# power_simp.net
KiCad netlist of a schematic drawn in Altium Designer
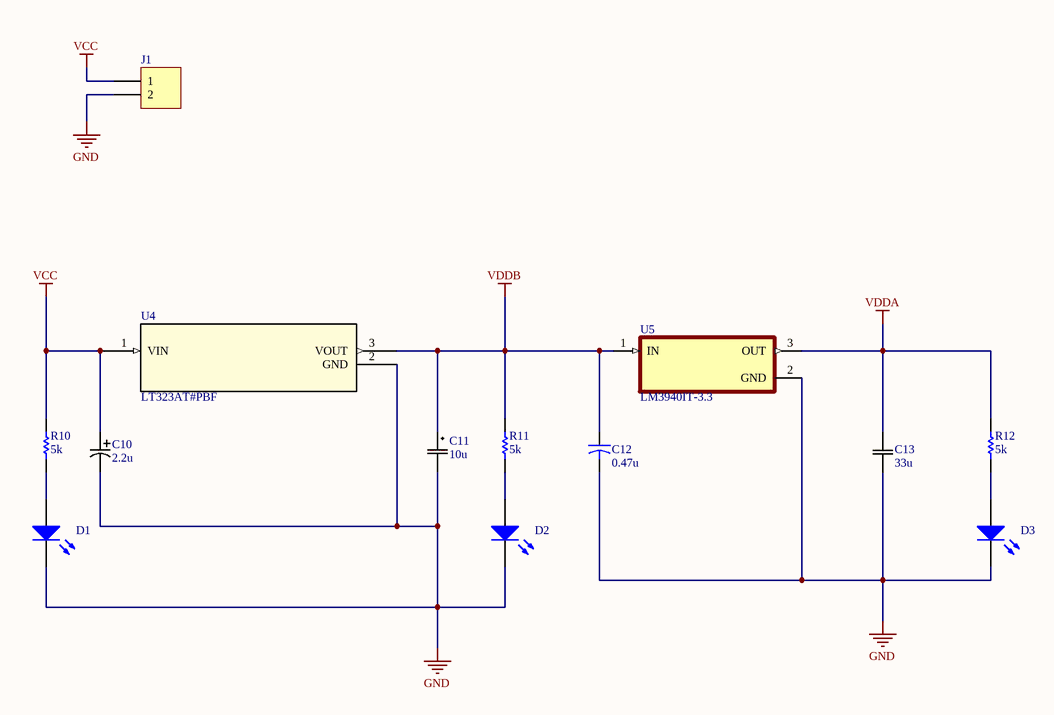
[diagram p0: power_simp.SchDoc]

(export (version "E")
  (design (tool "Eeschema 10.0.6"))
  (components
    (comp (ref "C10")
      (value "2.2u")
      (footprint "PCAP_3x5-THRU-ELECT_NCA")
      (description "No Description Available")
      (libsource (lib "UMA1V2R2MCD2") (part "UMA1V2R2MCD2"))
    )
    (comp (ref "C11")
      (value "10u")
      (footprint "CAP_UHC_4X7_NCH")
      (description "No Description Available")
      (libsource (lib "USR1E100MDD1TE") (part "USR1E100MDD1TE"))
    )
    (comp (ref "C12")
      (value "0.47u")
      (footprint "CAPR5-4X5")
      (description "Capacitor")
      (fields (field (name "Comment") "Cap2") (field (name "PUBLISHER") "Altium Limited"))
      (libsource (lib "Miscellaneous Devices") (part "Cap2"))
    )
    (comp (ref "C13")
      (value "33u")
      (footprint "CAP_FG16X5R1E336MRT06_TDK")
      (description "No Description Available")
      (libsource (lib "FG16X5R1E336MRT06") (part "FG16X5R1E336MRT06"))
    )
    (comp (ref "D1")
      (value "LED1")
      (footprint "LED-1")
      (description "Typical RED GaAs LED")
      (fields (field (name "PUBLISHER") "Altium Limited"))
      (libsource (lib "Miscellaneous Devices") (part "LED1"))
    )
    (comp (ref "D2")
      (value "LED1")
      (footprint "LED-1")
      (description "Typical RED GaAs LED")
      (fields (field (name "PUBLISHER") "Altium Limited"))
      (libsource (lib "Miscellaneous Devices") (part "LED1"))
    )
    (comp (ref "D3")
      (value "LED1")
      (footprint "LED-1")
      (description "Typical RED GaAs LED")
      (fields (field (name "PUBLISHER") "Altium Limited"))
      (libsource (lib "Miscellaneous Devices") (part "LED1"))
    )
    (comp (ref "J1")
      (value "Header 2")
      (footprint "HDR1X2")
      (description "Header, 2-Pin")
      (fields (field (name "PUBLISHER") "Altium Limited"))
      (libsource (lib "Miscellaneous Connectors") (part "Header 2"))
    )
    (comp (ref "R10")
      (value "5k")
      (footprint "AXIAL-0.3")
      (description "Resistor")
      (fields (field (name "Comment") "Res1") (field (name "PUBLISHER") "Altium Limited"))
      (libsource (lib "Miscellaneous Devices") (part "Res1"))
    )
    (comp (ref "R11")
      (value "5k")
      (footprint "AXIAL-0.3")
      (description "Resistor")
      (fields (field (name "Comment") "Res1") (field (name "PUBLISHER") "Altium Limited"))
      (libsource (lib "Miscellaneous Devices") (part "Res1"))
    )
    (comp (ref "R12")
      (value "5k")
      (footprint "AXIAL-0.3")
      (description "Resistor")
      (fields (field (name "Comment") "Res1") (field (name "PUBLISHER") "Altium Limited"))
      (libsource (lib "Miscellaneous Devices") (part "Res1"))
    )
    (comp (ref "U4")
      (value "LT323AT#PBF")
      (footprint "TO-220-AB")
      (description "No Description Available")
      (fields (field (name "COPYRIGHT") "Copyright (C) 2022 Ultra Librarian. All rights reserved."))
      (libsource (lib "LT323AT&hash_PBF") (part "LT323AT#PBF"))
    )
    (comp (ref "U5")
      (value "LM3940IT-3.3")
      (footprint "TO254P1054X470X1955-3:TO254P1054X470X1955-3")
      (description "1-A, low-dropout voltage regulator for 5-V to 3.3-V conversion 3-TO-220 -40 to 125")
      (fields (field (name "MF") "Texas Instruments"))
      (libsource (lib "LM3940IT-3.3") (part "LM3940IT-3.3"))
    )
  )
  (nets
    (net (code "1") (name "GND") (class "Default")
      (node (ref "C10") (pin "2") (pinfunction "2_2") (pintype "passive"))
      (node (ref "C11") (pin "2") (pinfunction "2_2") (pintype "passive"))
      (node (ref "C12") (pin "2") (pinfunction "2_2") (pintype "passive"))
      (node (ref "C13") (pin "1") (pinfunction "1_1") (pintype "passive"))
      (node (ref "D1") (pin "2") (pinfunction "K_2") (pintype "passive"))
      (node (ref "D2") (pin "2") (pinfunction "K_2") (pintype "passive"))
      (node (ref "D3") (pin "2") (pinfunction "K_2") (pintype "passive"))
      (node (ref "J1") (pin "2") (pinfunction "2_2") (pintype "passive"))
      (node (ref "U4") (pin "2") (pinfunction "GND_2") (pintype "power_in"))
      (node (ref "U5") (pin "2") (pinfunction "GND_2") (pintype "power_in"))
    )
    (net (code "2") (name "Net-(D1-A)") (class "Default")
      (node (ref "D1") (pin "1") (pinfunction "A_1") (pintype "passive"))
      (node (ref "R10") (pin "1") (pinfunction "1_1") (pintype "passive"))
    )
    (net (code "3") (name "Net-(D2-A)") (class "Default")
      (node (ref "D2") (pin "1") (pinfunction "A_1") (pintype "passive"))
      (node (ref "R11") (pin "1") (pinfunction "1_1") (pintype "passive"))
    )
    (net (code "4") (name "Net-(D3-A)") (class "Default")
      (node (ref "D3") (pin "1") (pinfunction "A_1") (pintype "passive"))
      (node (ref "R12") (pin "1") (pinfunction "1_1") (pintype "passive"))
    )
    (net (code "5") (name "VCC") (class "Default")
      (node (ref "C10") (pin "1") (pinfunction "1_1") (pintype "passive"))
      (node (ref "J1") (pin "1") (pinfunction "1_1") (pintype "passive"))
      (node (ref "R10") (pin "2") (pinfunction "2_2") (pintype "passive"))
      (node (ref "U4") (pin "1") (pinfunction "VIN_1") (pintype "input"))
    )
    (net (code "6") (name "VDDA") (class "Default")
      (node (ref "C13") (pin "2") (pinfunction "2_2") (pintype "passive"))
      (node (ref "R12") (pin "2") (pinfunction "2_2") (pintype "passive"))
      (node (ref "U5") (pin "3") (pinfunction "OUT_3") (pintype "output"))
    )
    (net (code "7") (name "VDDB") (class "Default")
      (node (ref "C11") (pin "1") (pinfunction "1_1") (pintype "passive"))
      (node (ref "C12") (pin "1") (pinfunction "1_1") (pintype "passive"))
      (node (ref "R11") (pin "2") (pinfunction "2_2") (pintype "passive"))
      (node (ref "U4") (pin "3") (pinfunction "VOUT_3") (pintype "output"))
      (node (ref "U5") (pin "1") (pinfunction "IN_1") (pintype "input"))
    )
  )
)
